# ICAN-7006-IO.net
KiCad netlist of a schematic drawn in Altium Designer
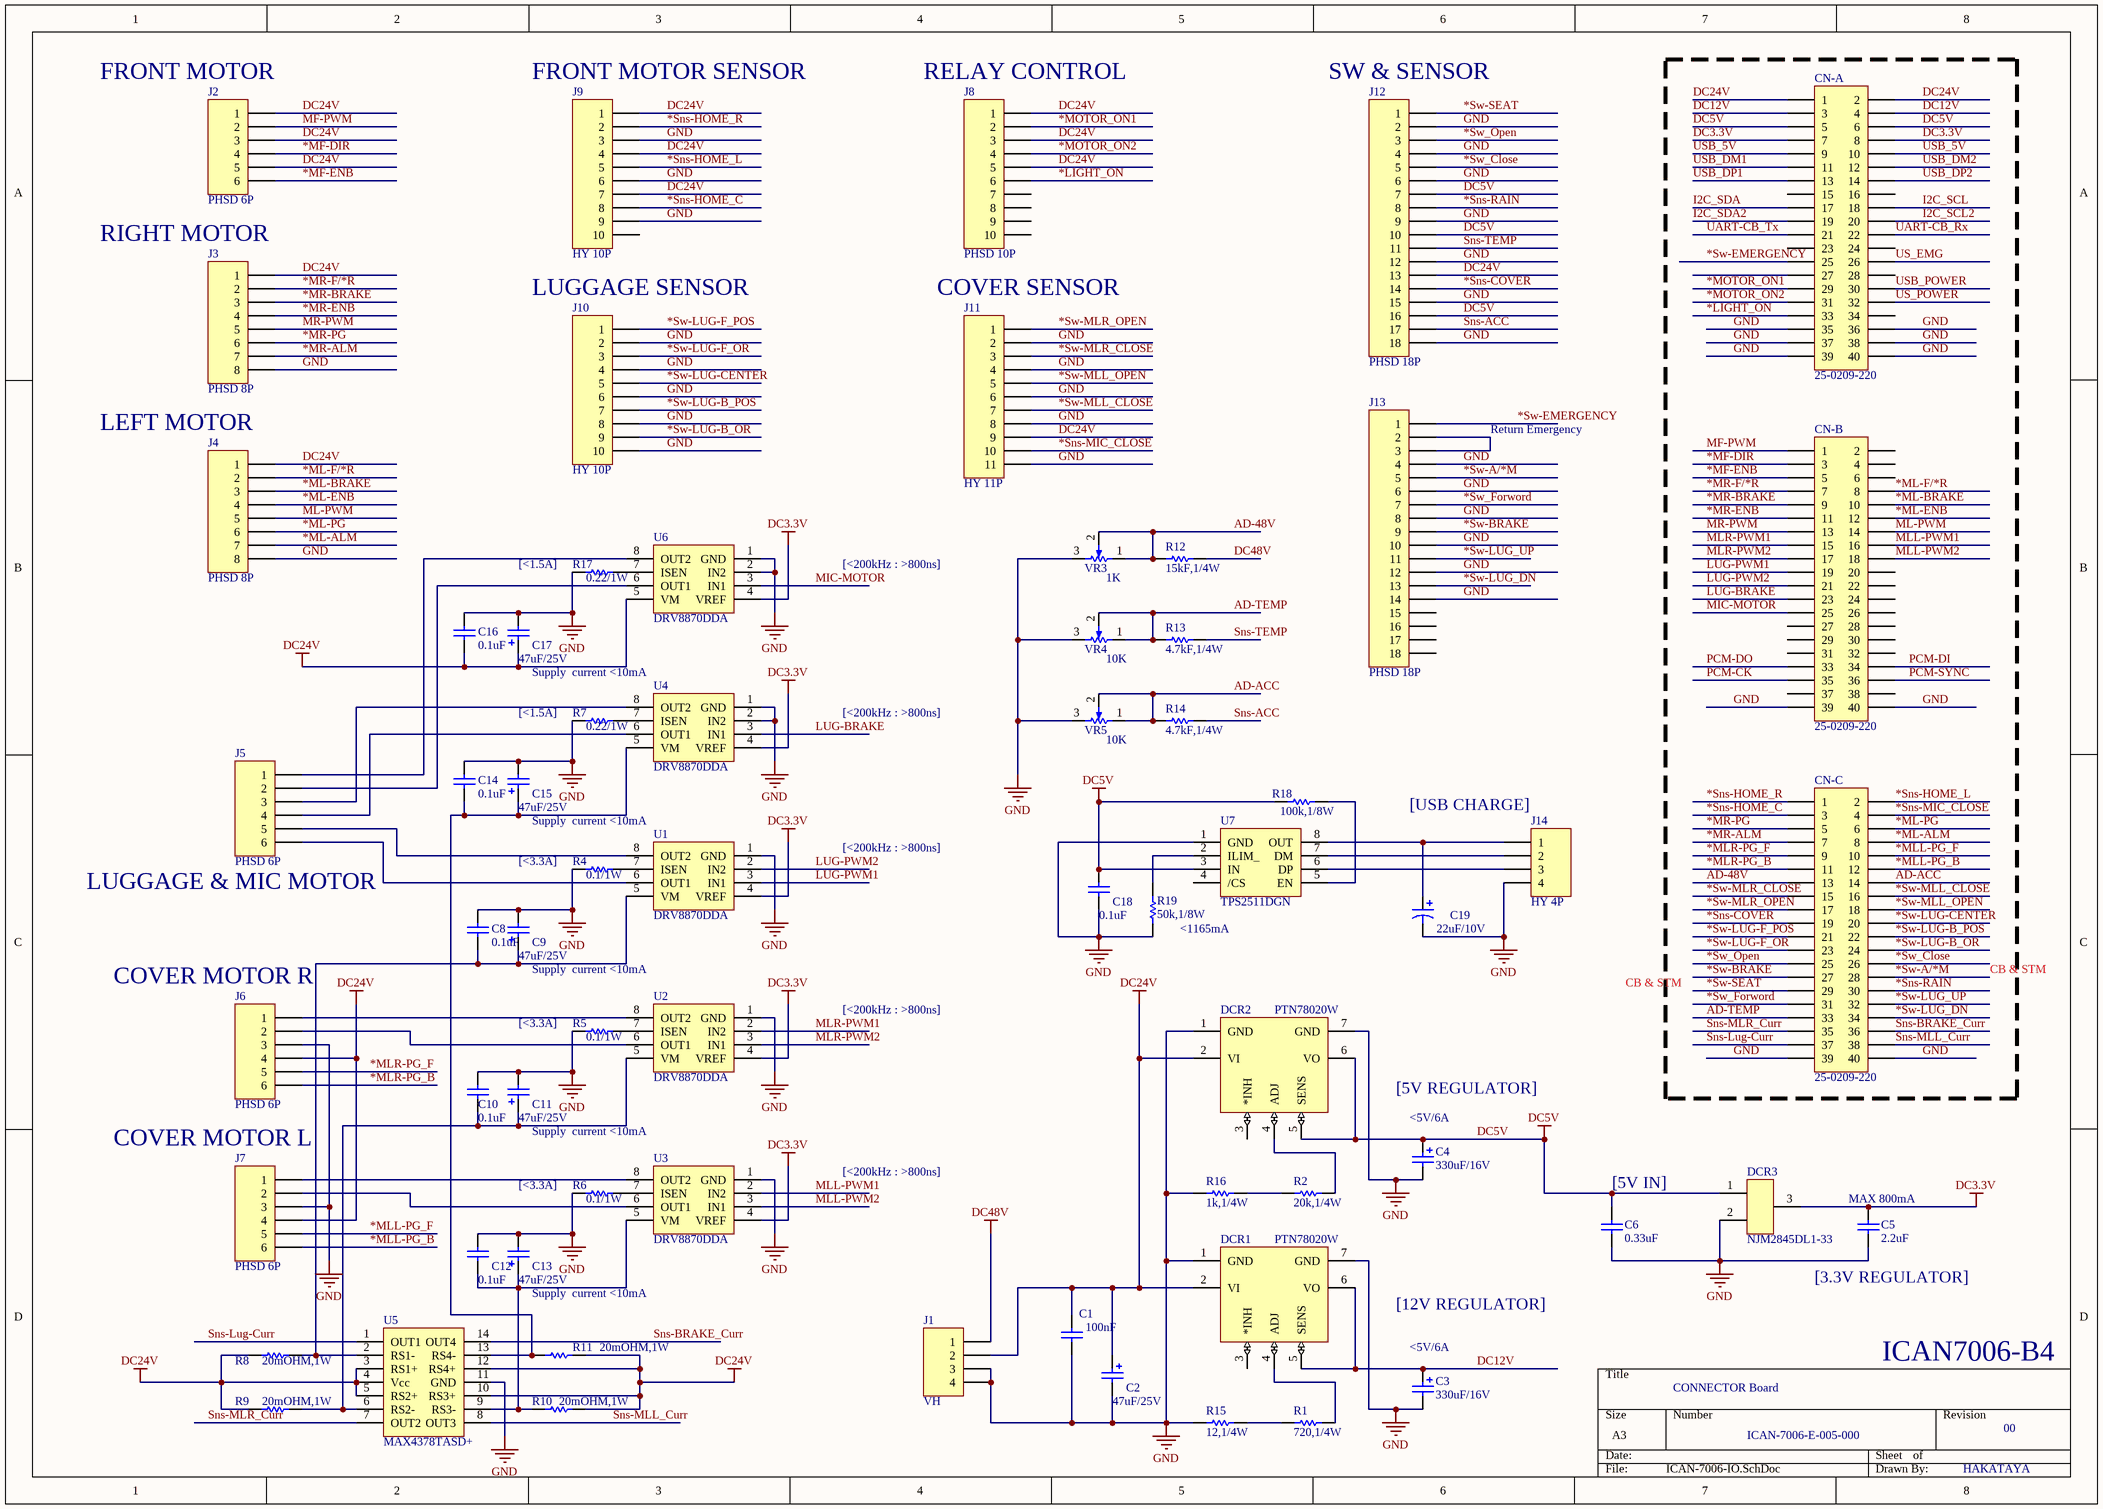
[diagram p0: ICAN-7006-IO.SchDoc]

(export (version "E")
  (design (tool "Eeschema 10.0.6"))
  (components
    (comp (ref "C1")
      (value "100nF")
      (footprint "HAKATAYA:[0805]2012")
      (description "Capacitor")
      (fields (field (name "PUBLISHER") "Altium Limited"))
      (libsource (lib "Miscellaneous Devices") (part "Cap"))
    )
    (comp (ref "C2")
      (value "47uF/25V")
      (footprint "HAKATAYA:Capa MH5 PITCH2.5mm")
      (description "Polarized Capacitor (Axial)")
      (fields (field (name "PUBLISHER") "Altium Limited"))
      (libsource (lib "Miscellaneous Devices") (part "Cap Pol2"))
    )
    (comp (ref "C3")
      (value "330uF/16V")
      (footprint "HAKATAYA:CAPA WXA PITCH 3.5mm")
      (description "Polarized Capacitor (Axial)")
      (fields (field (name "PUBLISHER") "Altium Limited"))
      (libsource (lib "Miscellaneous Devices") (part "Cap Pol2"))
    )
    (comp (ref "C4")
      (value "330uF/16V")
      (footprint "HAKATAYA:CAPA WXA PITCH 3.5mm")
      (description "Polarized Capacitor (Axial)")
      (fields (field (name "PUBLISHER") "Altium Limited"))
      (libsource (lib "Miscellaneous Devices") (part "Cap Pol2"))
    )
    (comp (ref "C5")
      (value "2.2uF")
      (footprint "[0805]2012")
      (description "Capacitor")
      (fields (field (name "PUBLISHER") "Altium Limited"))
      (libsource (lib "Miscellaneous Devices") (part "Cap Semi"))
    )
    (comp (ref "C6")
      (value "0.33uF")
      (footprint "[0805]2012")
      (description "Capacitor")
      (fields (field (name "PUBLISHER") "Altium Limited"))
      (libsource (lib "Miscellaneous Devices") (part "Cap Semi"))
    )
    (comp (ref "C8")
      (value "0.1uF")
      (footprint "HAKATAYA:[0805]2012")
      (description "Capacitor")
      (fields (field (name "PUBLISHER") "Altium Limited"))
      (libsource (lib "Miscellaneous Devices") (part "Cap"))
    )
    (comp (ref "C9")
      (value "47uF/25V")
      (footprint "HAKATAYA:Capa MH5 PITCH2.5mm")
      (description "Polarized Capacitor (Axial)")
      (fields (field (name "PUBLISHER") "Altium Limited"))
      (libsource (lib "Miscellaneous Devices") (part "Cap Pol2"))
    )
    (comp (ref "C10")
      (value "0.1uF")
      (footprint "HAKATAYA:[0805]2012")
      (description "Capacitor")
      (fields (field (name "PUBLISHER") "Altium Limited"))
      (libsource (lib "Miscellaneous Devices") (part "Cap"))
    )
    (comp (ref "C11")
      (value "47uF/25V")
      (footprint "HAKATAYA:Capa MH5 PITCH2.5mm")
      (description "Polarized Capacitor (Axial)")
      (fields (field (name "PUBLISHER") "Altium Limited"))
      (libsource (lib "Miscellaneous Devices") (part "Cap Pol2"))
    )
    (comp (ref "C12")
      (value "0.1uF")
      (footprint "HAKATAYA:[0805]2012")
      (description "Capacitor")
      (fields (field (name "PUBLISHER") "Altium Limited"))
      (libsource (lib "Miscellaneous Devices") (part "Cap"))
    )
    (comp (ref "C13")
      (value "47uF/25V")
      (footprint "HAKATAYA:Capa MH5 PITCH2.5mm")
      (description "Polarized Capacitor (Axial)")
      (fields (field (name "PUBLISHER") "Altium Limited"))
      (libsource (lib "Miscellaneous Devices") (part "Cap Pol2"))
    )
    (comp (ref "C14")
      (value "0.1uF")
      (footprint "HAKATAYA:[0805]2012")
      (description "Capacitor")
      (fields (field (name "PUBLISHER") "Altium Limited"))
      (libsource (lib "Miscellaneous Devices") (part "Cap"))
    )
    (comp (ref "C15")
      (value "47uF/25V")
      (footprint "HAKATAYA:Capa MH5 PITCH2.5mm")
      (description "Polarized Capacitor (Axial)")
      (fields (field (name "PUBLISHER") "Altium Limited"))
      (libsource (lib "Miscellaneous Devices") (part "Cap Pol2"))
    )
    (comp (ref "C16")
      (value "0.1uF")
      (footprint "HAKATAYA:[0805]2012")
      (description "Capacitor")
      (fields (field (name "PUBLISHER") "Altium Limited"))
      (libsource (lib "Miscellaneous Devices") (part "Cap"))
    )
    (comp (ref "C17")
      (value "47uF/25V")
      (footprint "HAKATAYA:Capa MH5 PITCH2.5mm")
      (description "Polarized Capacitor (Axial)")
      (fields (field (name "PUBLISHER") "Altium Limited"))
      (libsource (lib "Miscellaneous Devices") (part "Cap Pol2"))
    )
    (comp (ref "C18")
      (value "0.1uF")
      (footprint "HAKATAYA:[0805]2012")
      (description "Capacitor")
      (fields (field (name "PUBLISHER") "Altium Limited"))
      (libsource (lib "Miscellaneous Devices") (part "Cap"))
    )
    (comp (ref "C19")
      (value "22uF/10V")
      (footprint "[0805]2012")
      (description "Polarized Capacitor (Surface Mount)")
      (fields (field (name "PUBLISHER") "Altium Limited"))
      (libsource (lib "Miscellaneous Devices") (part "Cap Pol3"))
    )
    (comp (ref "CN-A")
      (value "25-0209-220")
      (footprint "HDR2X20")
      (description "Header, 20-Pin, Dual row")
      (fields (field (name "PUBLISHER") "Altium Limited"))
      (libsource (lib "Miscellaneous Connectors") (part "Header 20X2"))
    )
    (comp (ref "CN-B")
      (value "25-0209-220")
      (footprint "HDR2X20")
      (description "Header, 20-Pin, Dual row")
      (fields (field (name "PUBLISHER") "Altium Limited"))
      (libsource (lib "Miscellaneous Connectors") (part "Header 20X2"))
    )
    (comp (ref "CN-C")
      (value "25-0209-220")
      (footprint "HDR2X20")
      (description "Header, 20-Pin, Dual row")
      (fields (field (name "PUBLISHER") "Altium Limited"))
      (libsource (lib "Miscellaneous Connectors") (part "Header 20X2"))
    )
    (comp (ref "DCR1")
      (value "PTN78020W")
      (footprint "PTN78020")
      (description "REGULATOR")
      (libsource (lib "*") (part "PTN78020"))
    )
    (comp (ref "DCR2")
      (value "PTN78020W")
      (footprint "PTN78020")
      (description "REGULATOR")
      (libsource (lib "*") (part "PTN78020"))
    )
    (comp (ref "DCR3")
      (value "NJM2845DL1-33")
      (footprint "TO-252-3")
      (description "REGURATOR")
      (libsource (lib "HAKATAYA") (part "IC3"))
    )
    (comp (ref "J1")
      (value "VH")
      (footprint "HAKATAYA:VH-S4")
      (description "Header, 4-Pin")
      (fields (field (name "PUBLISHER") "Altium Limited"))
      (libsource (lib "Miscellaneous Connectors") (part "Header 4"))
    )
    (comp (ref "J2")
      (value "PHSD 6P")
      (footprint "HAKATAYA:PHSD WV03x2")
      (description "Header, 6-Pin")
      (fields (field (name "PUBLISHER") "Altium Limited"))
      (libsource (lib "Miscellaneous Connectors") (part "Header 6"))
    )
    (comp (ref "J3")
      (value "PHSD 8P")
      (footprint "HAKATAYA:PHSD WV04x2")
      (description "Header, 8-Pin")
      (fields (field (name "PUBLISHER") "Altium Limited"))
      (libsource (lib "Miscellaneous Connectors") (part "Header 8"))
    )
    (comp (ref "J4")
      (value "PHSD 8P")
      (footprint "HAKATAYA:PHSD WV04x2")
      (description "Header, 8-Pin")
      (fields (field (name "PUBLISHER") "Altium Limited"))
      (libsource (lib "Miscellaneous Connectors") (part "Header 8"))
    )
    (comp (ref "J5")
      (value "PHSD 6P")
      (footprint "HAKATAYA:PHSD WV03x2")
      (description "Header, 6-Pin")
      (fields (field (name "PUBLISHER") "Altium Limited"))
      (libsource (lib "Miscellaneous Connectors") (part "Header 6"))
    )
    (comp (ref "J6")
      (value "PHSD 6P")
      (footprint "HAKATAYA:PHSD WV03x2")
      (description "Header, 6-Pin")
      (fields (field (name "PUBLISHER") "Altium Limited"))
      (libsource (lib "Miscellaneous Connectors") (part "Header 6"))
    )
    (comp (ref "J7")
      (value "PHSD 6P")
      (footprint "HAKATAYA:PHSD WV03x2")
      (description "Header, 6-Pin")
      (fields (field (name "PUBLISHER") "Altium Limited"))
      (libsource (lib "Miscellaneous Connectors") (part "Header 6"))
    )
    (comp (ref "J8")
      (value "PHSD 10P")
      (footprint "HAKATAYA:PHSD WV05x2")
      (description "Header, 10-Pin")
      (fields (field (name "PUBLISHER") "Altium Limited"))
      (libsource (lib "Miscellaneous Connectors") (part "Header 10"))
    )
    (comp (ref "J9")
      (value "HY 10P")
      (footprint "HAKATAYA:HY-10A")
      (description "Header, 10-Pin")
      (fields (field (name "PUBLISHER") "Altium Limited"))
      (libsource (lib "Miscellaneous Connectors") (part "Header 10"))
    )
    (comp (ref "J10")
      (value "HY 10P")
      (footprint "HAKATAYA:HY-10A")
      (description "Header, 10-Pin")
      (fields (field (name "PUBLISHER") "Altium Limited"))
      (libsource (lib "Miscellaneous Connectors") (part "Header 10"))
    )
    (comp (ref "J11")
      (value "HY 11P")
      (footprint "HAKATAYA:HY-11A")
      (description "Header, 11-Pin")
      (fields (field (name "PUBLISHER") "Altium Limited"))
      (libsource (lib "Miscellaneous Connectors") (part "Header 11"))
    )
    (comp (ref "J12")
      (value "PHSD 18P")
      (footprint "HAKATAYA:PHSD WV09X2")
      (description "Header, 18-Pin")
      (fields (field (name "PUBLISHER") "Altium Limited"))
      (libsource (lib "Miscellaneous Connectors") (part "Header 18"))
    )
    (comp (ref "J13")
      (value "PHSD 18P")
      (footprint "HAKATAYA:PHSD WV09X2")
      (description "Header, 18-Pin")
      (fields (field (name "PUBLISHER") "Altium Limited"))
      (libsource (lib "Miscellaneous Connectors") (part "Header 18"))
    )
    (comp (ref "J14")
      (value "HY 4P")
      (footprint "HAKATAYA:HY-4A")
      (description "Header, 4-Pin")
      (fields (field (name "PUBLISHER") "Altium Limited"))
      (libsource (lib "") (part "Header 4_1"))
    )
    (comp (ref "R1")
      (value "720,1/4W")
      (footprint "HAKATAYA:[1206]3216")
      (description "Resistor")
      (fields (field (name "PUBLISHER") "Altium Limited"))
      (libsource (lib "Miscellaneous Devices") (part "Res1"))
    )
    (comp (ref "R2")
      (value "20k,1/4W")
      (footprint "HAKATAYA:[1206]3216")
      (description "Resistor")
      (fields (field (name "PUBLISHER") "Altium Limited"))
      (libsource (lib "Miscellaneous Devices") (part "Res1"))
    )
    (comp (ref "R4")
      (value "0.1/1W")
      (footprint "[1206]3216")
      (description "Resistor")
      (fields (field (name "PUBLISHER") "Altium Limited"))
      (libsource (lib "Miscellaneous Devices") (part "Res1"))
    )
    (comp (ref "R5")
      (value "0.1/1W")
      (footprint "[1206]3216")
      (description "Resistor")
      (fields (field (name "PUBLISHER") "Altium Limited"))
      (libsource (lib "Miscellaneous Devices") (part "Res1"))
    )
    (comp (ref "R6")
      (value "0.1/1W")
      (footprint "[1206]3216")
      (description "Resistor")
      (fields (field (name "PUBLISHER") "Altium Limited"))
      (libsource (lib "Miscellaneous Devices") (part "Res1"))
    )
    (comp (ref "R7")
      (value "0.22/1W")
      (footprint "HAKATAYA:[1206]3216")
      (description "Resistor")
      (fields (field (name "PUBLISHER") "Altium Limited"))
      (libsource (lib "Miscellaneous Devices") (part "Res1"))
    )
    (comp (ref "R8")
      (value "20mOHM,1W")
      (footprint "Miscellaneous Devices:6332[2512]")
      (description "Resistor")
      (fields (field (name "PUBLISHER") "Altium Limited"))
      (libsource (lib "Miscellaneous Devices") (part "Res1"))
    )
    (comp (ref "R9")
      (value "20mOHM,1W")
      (footprint "Miscellaneous Devices:6332[2512]")
      (description "Resistor")
      (fields (field (name "PUBLISHER") "Altium Limited"))
      (libsource (lib "Miscellaneous Devices") (part "Res1"))
    )
    (comp (ref "R10")
      (value "20mOHM,1W")
      (footprint "Miscellaneous Devices:6332[2512]")
      (description "Resistor")
      (fields (field (name "PUBLISHER") "Altium Limited"))
      (libsource (lib "Miscellaneous Devices") (part "Res1"))
    )
    (comp (ref "R11")
      (value "20mOHM,1W")
      (footprint "Miscellaneous Devices:6332[2512]")
      (description "Resistor")
      (fields (field (name "PUBLISHER") "Altium Limited"))
      (libsource (lib "Miscellaneous Devices") (part "Res1"))
    )
    (comp (ref "R12")
      (value "15kF,1/4W")
      (footprint "HAKATAYA:[1206]3216")
      (description "Resistor")
      (fields (field (name "PUBLISHER") "Altium Limited"))
      (libsource (lib "Miscellaneous Devices") (part "Res1"))
    )
    (comp (ref "R13")
      (value "4.7kF,1/4W")
      (footprint "[1206]3216")
      (description "Resistor")
      (fields (field (name "PUBLISHER") "Altium Limited"))
      (libsource (lib "Miscellaneous Devices") (part "Res1"))
    )
    (comp (ref "R14")
      (value "4.7kF,1/4W")
      (footprint "[1206]3216")
      (description "Resistor")
      (fields (field (name "PUBLISHER") "Altium Limited"))
      (libsource (lib "Miscellaneous Devices") (part "Res1"))
    )
    (comp (ref "R15")
      (value "12,1/4W")
      (footprint "HAKATAYA:[1206]3216")
      (description "Resistor")
      (fields (field (name "PUBLISHER") "Altium Limited"))
      (libsource (lib "Miscellaneous Devices") (part "Res1"))
    )
    (comp (ref "R16")
      (value "1k,1/4W")
      (footprint "HAKATAYA:[1206]3216")
      (description "Resistor")
      (fields (field (name "PUBLISHER") "Altium Limited"))
      (libsource (lib "Miscellaneous Devices") (part "Res1"))
    )
    (comp (ref "R17")
      (value "0.22/1W")
      (footprint "HAKATAYA:[1206]3216")
      (description "Resistor")
      (fields (field (name "PUBLISHER") "Altium Limited"))
      (libsource (lib "Miscellaneous Devices") (part "Res1"))
    )
    (comp (ref "R18")
      (value "100k,1/8W")
      (footprint "HAKATAYA:[0805]2012")
      (description "Resistor")
      (fields (field (name "PUBLISHER") "Altium Limited"))
      (libsource (lib "Miscellaneous Devices") (part "Res1"))
    )
    (comp (ref "R19")
      (value "50k,1/8W")
      (footprint "HAKATAYA:[0805]2012")
      (description "Resistor")
      (fields (field (name "PUBLISHER") "Altium Limited"))
      (libsource (lib "Miscellaneous Devices") (part "Res1"))
    )
    (comp (ref "U1")
      (value "DRV8870DDA")
      (footprint "TI Interface MOSFET Driver:D008_L")
      (description "Motor Driver")
      (libsource (lib "HAKATAYA") (part "IC8-WIDE"))
    )
    (comp (ref "U2")
      (value "DRV8870DDA")
      (footprint "TI Interface MOSFET Driver:D008_L")
      (description "Motor Driver")
      (libsource (lib "HAKATAYA") (part "IC8-WIDE"))
    )
    (comp (ref "U3")
      (value "DRV8870DDA")
      (footprint "TI Interface MOSFET Driver:D008_L")
      (description "Motor Driver")
      (libsource (lib "HAKATAYA") (part "IC8-WIDE"))
    )
    (comp (ref "U4")
      (value "DRV8870DDA")
      (footprint "TI Interface MOSFET Driver:D008_L")
      (description "Motor Driver")
      (libsource (lib "HAKATAYA") (part "IC8-WIDE"))
    )
    (comp (ref "U5")
      (value "MAX4378TASD+")
      (footprint "Microchip Footprints:SOIC150-14_L")
      (description "Current-Sense")
      (libsource (lib "*") (part "IC14"))
    )
    (comp (ref "U6")
      (value "DRV8870DDA")
      (footprint "TI Interface MOSFET Driver:D008_L")
      (description "Motor Driver")
      (libsource (lib "HAKATAYA") (part "IC8-WIDE"))
    )
    (comp (ref "U7")
      (value "TPS2511DGN")
      (footprint "HAKATAYA:DGN 8P")
      (description "Power Switch")
      (libsource (lib "") (part "IC8-WIDE_1"))
    )
    (comp (ref "VR3")
      (value "1K")
      (footprint "VR")
      (description "Square Trimming Potentiometer")
      (fields (field (name "PUBLISHER") "Altium Limited"))
      (libsource (lib "Miscellaneous Devices") (part "RPot SM"))
    )
    (comp (ref "VR4")
      (value "10K")
      (footprint "VR")
      (description "Square Trimming Potentiometer")
      (fields (field (name "PUBLISHER") "Altium Limited"))
      (libsource (lib "Miscellaneous Devices") (part "RPot SM"))
    )
    (comp (ref "VR5")
      (value "10K")
      (footprint "VR")
      (description "Square Trimming Potentiometer")
      (fields (field (name "PUBLISHER") "Altium Limited"))
      (libsource (lib "Miscellaneous Devices") (part "RPot SM"))
    )
  )
  (nets
    (net (code "1") (name "/*LIGHT_ON") (class "Default")
      (node (ref "CN-A") (pin "33") (pinfunction "33_33") (pintype "passive"))
      (node (ref "J8") (pin "6") (pinfunction "6_6") (pintype "passive"))
    )
    (net (code "2") (name "/*MF-DIR") (class "Default")
      (node (ref "CN-B") (pin "3") (pinfunction "3_3") (pintype "passive"))
      (node (ref "J2") (pin "4") (pinfunction "4_4") (pintype "passive"))
    )
    (net (code "3") (name "/*MF-ENB") (class "Default")
      (node (ref "CN-B") (pin "5") (pinfunction "5_5") (pintype "passive"))
      (node (ref "J2") (pin "6") (pinfunction "6_6") (pintype "passive"))
    )
    (net (code "4") (name "/*ML-ALM") (class "Default")
      (node (ref "CN-C") (pin "8") (pinfunction "8_8") (pintype "passive"))
      (node (ref "J4") (pin "7") (pinfunction "7_7") (pintype "passive"))
    )
    (net (code "5") (name "/*ML-BRAKE") (class "Default")
      (node (ref "CN-B") (pin "10") (pinfunction "10_10") (pintype "passive"))
      (node (ref "J4") (pin "3") (pinfunction "3_3") (pintype "passive"))
    )
    (net (code "6") (name "/*ML-ENB") (class "Default")
      (node (ref "CN-B") (pin "12") (pinfunction "12_12") (pintype "passive"))
      (node (ref "J4") (pin "4") (pinfunction "4_4") (pintype "passive"))
    )
    (net (code "7") (name "/*ML-F{slash}*R") (class "Default")
      (node (ref "CN-B") (pin "8") (pinfunction "8_8") (pintype "passive"))
      (node (ref "J4") (pin "2") (pinfunction "2_2") (pintype "passive"))
    )
    (net (code "8") (name "/*ML-PG") (class "Default")
      (node (ref "CN-C") (pin "6") (pinfunction "6_6") (pintype "passive"))
      (node (ref "J4") (pin "6") (pinfunction "6_6") (pintype "passive"))
    )
    (net (code "9") (name "/*MLL-PG_B") (class "Default")
      (node (ref "CN-C") (pin "12") (pinfunction "12_12") (pintype "passive"))
      (node (ref "J7") (pin "6") (pinfunction "6_6") (pintype "passive"))
    )
    (net (code "10") (name "/*MLL-PG_F") (class "Default")
      (node (ref "CN-C") (pin "10") (pinfunction "10_10") (pintype "passive"))
      (node (ref "J7") (pin "5") (pinfunction "5_5") (pintype "passive"))
    )
    (net (code "11") (name "/*MLR-PG_B") (class "Default")
      (node (ref "CN-C") (pin "11") (pinfunction "11_11") (pintype "passive"))
      (node (ref "J6") (pin "6") (pinfunction "6_6") (pintype "passive"))
    )
    (net (code "12") (name "/*MLR-PG_F") (class "Default")
      (node (ref "CN-C") (pin "9") (pinfunction "9_9") (pintype "passive"))
      (node (ref "J6") (pin "5") (pinfunction "5_5") (pintype "passive"))
    )
    (net (code "13") (name "/*MOTOR_ON1") (class "Default")
      (node (ref "CN-A") (pin "29") (pinfunction "29_29") (pintype "passive"))
      (node (ref "J8") (pin "2") (pinfunction "2_2") (pintype "passive"))
    )
    (net (code "14") (name "/*MOTOR_ON2") (class "Default")
      (node (ref "CN-A") (pin "31") (pinfunction "31_31") (pintype "passive"))
      (node (ref "J8") (pin "4") (pinfunction "4_4") (pintype "passive"))
    )
    (net (code "15") (name "/*MR-ALM") (class "Default")
      (node (ref "CN-C") (pin "7") (pinfunction "7_7") (pintype "passive"))
      (node (ref "J3") (pin "7") (pinfunction "7_7") (pintype "passive"))
    )
    (net (code "16") (name "/*MR-BRAKE") (class "Default")
      (node (ref "CN-B") (pin "9") (pinfunction "9_9") (pintype "passive"))
      (node (ref "J3") (pin "3") (pinfunction "3_3") (pintype "passive"))
    )
    (net (code "17") (name "/*MR-ENB") (class "Default")
      (node (ref "CN-B") (pin "11") (pinfunction "11_11") (pintype "passive"))
      (node (ref "J3") (pin "4") (pinfunction "4_4") (pintype "passive"))
    )
    (net (code "18") (name "/*MR-F{slash}*R") (class "Default")
      (node (ref "CN-B") (pin "7") (pinfunction "7_7") (pintype "passive"))
      (node (ref "J3") (pin "2") (pinfunction "2_2") (pintype "passive"))
    )
    (net (code "19") (name "/*MR-PG") (class "Default")
      (node (ref "CN-C") (pin "5") (pinfunction "5_5") (pintype "passive"))
      (node (ref "J3") (pin "6") (pinfunction "6_6") (pintype "passive"))
    )
    (net (code "20") (name "/*Sns-COVER") (class "Default")
      (node (ref "CN-C") (pin "19") (pinfunction "19_19") (pintype "passive"))
      (node (ref "J12") (pin "14") (pinfunction "14_14") (pintype "passive"))
    )
    (net (code "21") (name "/*Sns-HOME_C") (class "Default")
      (node (ref "CN-C") (pin "3") (pinfunction "3_3") (pintype "passive"))
      (node (ref "J9") (pin "8") (pinfunction "8_8") (pintype "passive"))
    )
    (net (code "22") (name "/*Sns-HOME_L") (class "Default")
      (node (ref "CN-C") (pin "2") (pinfunction "2_2") (pintype "passive"))
      (node (ref "J9") (pin "5") (pinfunction "5_5") (pintype "passive"))
    )
    (net (code "23") (name "/*Sns-HOME_R") (class "Default")
      (node (ref "CN-C") (pin "1") (pinfunction "1_1") (pintype "passive"))
      (node (ref "J9") (pin "2") (pinfunction "2_2") (pintype "passive"))
    )
    (net (code "24") (name "/*Sns-MIC_CLOSE") (class "Default")
      (node (ref "CN-C") (pin "4") (pinfunction "4_4") (pintype "passive"))
      (node (ref "J11") (pin "10") (pinfunction "10_10") (pintype "passive"))
    )
    (net (code "25") (name "/*Sns-RAIN") (class "Default")
      (node (ref "CN-C") (pin "30") (pinfunction "30_30") (pintype "passive"))
      (node (ref "J12") (pin "8") (pinfunction "8_8") (pintype "passive"))
    )
    (net (code "26") (name "/*Sw-A{slash}*M") (class "Default")
      (node (ref "CN-C") (pin "28") (pinfunction "28_28") (pintype "passive"))
      (node (ref "J13") (pin "5") (pinfunction "5_5") (pintype "passive"))
    )
    (net (code "27") (name "/*Sw-BRAKE") (class "Default")
      (node (ref "CN-C") (pin "27") (pinfunction "27_27") (pintype "passive"))
      (node (ref "J13") (pin "9") (pinfunction "9_9") (pintype "passive"))
    )
    (net (code "28") (name "/*Sw-EMERGENCY") (class "Default")
      (node (ref "CN-A") (pin "25") (pinfunction "25_25") (pintype "passive"))
      (node (ref "J13") (pin "1") (pinfunction "1_1") (pintype "passive"))
    )
    (net (code "29") (name "/*Sw-LUG-B_OR") (class "Default")
      (node (ref "CN-C") (pin "24") (pinfunction "24_24") (pintype "passive"))
      (node (ref "J10") (pin "9") (pinfunction "9_9") (pintype "passive"))
    )
    (net (code "30") (name "/*Sw-LUG-B_POS") (class "Default")
      (node (ref "CN-C") (pin "22") (pinfunction "22_22") (pintype "passive"))
      (node (ref "J10") (pin "7") (pinfunction "7_7") (pintype "passive"))
    )
    (net (code "31") (name "/*Sw-LUG-CENTER") (class "Default")
      (node (ref "CN-C") (pin "20") (pinfunction "20_20") (pintype "passive"))
      (node (ref "J10") (pin "5") (pinfunction "5_5") (pintype "passive"))
    )
    (net (code "32") (name "/*Sw-LUG-F_OR") (class "Default")
      (node (ref "CN-C") (pin "23") (pinfunction "23_23") (pintype "passive"))
      (node (ref "J10") (pin "3") (pinfunction "3_3") (pintype "passive"))
    )
    (net (code "33") (name "/*Sw-LUG-F_POS") (class "Default")
      (node (ref "CN-C") (pin "21") (pinfunction "21_21") (pintype "passive"))
      (node (ref "J10") (pin "1") (pinfunction "1_1") (pintype "passive"))
    )
    (net (code "34") (name "/*Sw-LUG_DN") (class "Default")
      (node (ref "CN-C") (pin "34") (pinfunction "34_34") (pintype "passive"))
      (node (ref "J13") (pin "13") (pinfunction "13_13") (pintype "passive"))
    )
    (net (code "35") (name "/*Sw-LUG_UP") (class "Default")
      (node (ref "CN-C") (pin "32") (pinfunction "32_32") (pintype "passive"))
      (node (ref "J13") (pin "11") (pinfunction "11_11") (pintype "passive"))
    )
    (net (code "36") (name "/*Sw-MLL_CLOSE") (class "Default")
      (node (ref "CN-C") (pin "16") (pinfunction "16_16") (pintype "passive"))
      (node (ref "J11") (pin "7") (pinfunction "7_7") (pintype "passive"))
    )
    (net (code "37") (name "/*Sw-MLL_OPEN") (class "Default")
      (node (ref "CN-C") (pin "18") (pinfunction "18_18") (pintype "passive"))
      (node (ref "J11") (pin "5") (pinfunction "5_5") (pintype "passive"))
    )
    (net (code "38") (name "/*Sw-MLR_CLOSE") (class "Default")
      (node (ref "CN-C") (pin "15") (pinfunction "15_15") (pintype "passive"))
      (node (ref "J11") (pin "3") (pinfunction "3_3") (pintype "passive"))
    )
    (net (code "39") (name "/*Sw-MLR_OPEN") (class "Default")
      (node (ref "CN-C") (pin "17") (pinfunction "17_17") (pintype "passive"))
      (node (ref "J11") (pin "1") (pinfunction "1_1") (pintype "passive"))
    )
    (net (code "40") (name "/*Sw-SEAT") (class "Default")
      (node (ref "CN-C") (pin "29") (pinfunction "29_29") (pintype "passive"))
      (node (ref "J12") (pin "1") (pinfunction "1_1") (pintype "passive"))
    )
    (net (code "41") (name "/*Sw_Close") (class "Default")
      (node (ref "CN-C") (pin "26") (pinfunction "26_26") (pintype "passive"))
      (node (ref "J12") (pin "5") (pinfunction "5_5") (pintype "passive"))
    )
    (net (code "42") (name "/*Sw_Forword") (class "Default")
      (node (ref "CN-C") (pin "31") (pinfunction "31_31") (pintype "passive"))
      (node (ref "J13") (pin "7") (pinfunction "7_7") (pintype "passive"))
    )
    (net (code "43") (name "/*Sw_Open") (class "Default")
      (node (ref "CN-C") (pin "25") (pinfunction "25_25") (pintype "passive"))
      (node (ref "J12") (pin "3") (pinfunction "3_3") (pintype "passive"))
    )
    (net (code "44") (name "/AD-48V") (class "Default")
      (node (ref "CN-C") (pin "13") (pinfunction "13_13") (pintype "passive"))
      (node (ref "R12") (pin "1") (pinfunction "1_1") (pintype "passive"))
      (node (ref "VR3") (pin "1") (pinfunction "1_1") (pintype "passive"))
      (node (ref "VR3") (pin "2") (pinfunction "3_2") (pintype "passive"))
    )
    (net (code "45") (name "/AD-ACC") (class "Default")
      (node (ref "CN-C") (pin "14") (pinfunction "14_14") (pintype "passive"))
      (node (ref "R14") (pin "1") (pinfunction "1_1") (pintype "passive"))
      (node (ref "VR5") (pin "1") (pinfunction "1_1") (pintype "passive"))
      (node (ref "VR5") (pin "2") (pinfunction "3_2") (pintype "passive"))
    )
    (net (code "46") (name "/AD-TEMP") (class "Default")
      (node (ref "CN-C") (pin "33") (pinfunction "33_33") (pintype "passive"))
      (node (ref "R13") (pin "1") (pinfunction "1_1") (pintype "passive"))
      (node (ref "VR4") (pin "1") (pinfunction "1_1") (pintype "passive"))
      (node (ref "VR4") (pin "2") (pinfunction "3_2") (pintype "passive"))
    )
    (net (code "47") (name "/DC12V") (class "Default")
      (node (ref "C3") (pin "1") (pinfunction "1_1") (pintype "passive"))
      (node (ref "CN-A") (pin "3") (pinfunction "3_3") (pintype "passive"))
      (node (ref "CN-A") (pin "4") (pinfunction "4_4") (pintype "passive"))
      (node (ref "DCR1") (pin "5") (pinfunction "SENS_5") (pintype "bidirectional"))
      (node (ref "DCR1") (pin "6") (pinfunction "VO_6") (pintype "power_in"))
    )
    (net (code "48") (name "/I2C_SCL") (class "Default")
      (node (ref "CN-A") (pin "18") (pinfunction "18_18") (pintype "passive"))
    )
    (net (code "49") (name "/I2C_SCL2") (class "Default")
      (node (ref "CN-A") (pin "20") (pinfunction "20_20") (pintype "passive"))
    )
    (net (code "50") (name "/I2C_SDA") (class "Default")
      (node (ref "CN-A") (pin "17") (pinfunction "17_17") (pintype "passive"))
    )
    (net (code "51") (name "/I2C_SDA2") (class "Default")
      (node (ref "CN-A") (pin "19") (pinfunction "19_19") (pintype "passive"))
    )
    (net (code "52") (name "/LUG-BRAKE") (class "Default")
      (node (ref "CN-B") (pin "23") (pinfunction "23_23") (pintype "passive"))
      (node (ref "U4") (pin "3") (pinfunction "IN1_3") (pintype "passive"))
    )
    (net (code "53") (name "/LUG-PWM1") (class "Default")
      (node (ref "CN-B") (pin "19") (pinfunction "19_19") (pintype "passive"))
      (node (ref "U1") (pin "3") (pinfunction "IN1_3") (pintype "passive"))
    )
    (net (code "54") (name "/LUG-PWM2") (class "Default")
      (node (ref "CN-B") (pin "21") (pinfunction "21_21") (pintype "passive"))
      (node (ref "U1") (pin "2") (pinfunction "IN2_2") (pintype "passive"))
    )
    (net (code "55") (name "/MF-PWM") (class "Default")
      (node (ref "CN-B") (pin "1") (pinfunction "1_1") (pintype "passive"))
      (node (ref "J2") (pin "2") (pinfunction "2_2") (pintype "passive"))
    )
    (net (code "56") (name "/MIC-MOTOR") (class "Default")
      (node (ref "CN-B") (pin "25") (pinfunction "25_25") (pintype "passive"))
      (node (ref "U6") (pin "3") (pinfunction "IN1_3") (pintype "passive"))
    )
    (net (code "57") (name "/ML-PWM") (class "Default")
      (node (ref "CN-B") (pin "14") (pinfunction "14_14") (pintype "passive"))
      (node (ref "J4") (pin "5") (pinfunction "5_5") (pintype "passive"))
    )
    (net (code "58") (name "/MLL-PWM1") (class "Default")
      (node (ref "CN-B") (pin "16") (pinfunction "16_16") (pintype "passive"))
      (node (ref "U3") (pin "2") (pinfunction "IN2_2") (pintype "passive"))
    )
    (net (code "59") (name "/MLL-PWM2") (class "Default")
      (node (ref "CN-B") (pin "18") (pinfunction "18_18") (pintype "passive"))
      (node (ref "U3") (pin "3") (pinfunction "IN1_3") (pintype "passive"))
    )
    (net (code "60") (name "/MLR-PWM1") (class "Default")
      (node (ref "CN-B") (pin "15") (pinfunction "15_15") (pintype "passive"))
      (node (ref "U2") (pin "2") (pinfunction "IN2_2") (pintype "passive"))
    )
    (net (code "61") (name "/MLR-PWM2") (class "Default")
      (node (ref "CN-B") (pin "17") (pinfunction "17_17") (pintype "passive"))
      (node (ref "U2") (pin "3") (pinfunction "IN1_3") (pintype "passive"))
    )
    (net (code "62") (name "/MR-PWM") (class "Default")
      (node (ref "CN-B") (pin "13") (pinfunction "13_13") (pintype "passive"))
      (node (ref "J3") (pin "5") (pinfunction "5_5") (pintype "passive"))
    )
    (net (code "63") (name "/PCM-CK") (class "Default")
      (node (ref "CN-B") (pin "35") (pinfunction "35_35") (pintype "passive"))
    )
    (net (code "64") (name "/PCM-DI") (class "Default")
      (node (ref "CN-B") (pin "34") (pinfunction "34_34") (pintype "passive"))
    )
    (net (code "65") (name "/PCM-DO") (class "Default")
      (node (ref "CN-B") (pin "33") (pinfunction "33_33") (pintype "passive"))
    )
    (net (code "66") (name "/PCM-SYNC") (class "Default")
      (node (ref "CN-B") (pin "36") (pinfunction "36_36") (pintype "passive"))
    )
    (net (code "67") (name "/Sns-ACC") (class "Default")
      (node (ref "J12") (pin "17") (pinfunction "17_17") (pintype "passive"))
      (node (ref "R14") (pin "2") (pinfunction "2_2") (pintype "passive"))
    )
    (net (code "68") (name "/Sns-BRAKE_Curr") (class "Default")
      (node (ref "CN-C") (pin "36") (pinfunction "36_36") (pintype "passive"))
      (node (ref "U5") (pin "14") (pinfunction "OUT4_14") (pintype "passive"))
    )
    (net (code "69") (name "/Sns-Lug-Curr") (class "Default")
      (node (ref "CN-C") (pin "37") (pinfunction "37_37") (pintype "passive"))
      (node (ref "U5") (pin "1") (pinfunction "OUT1_1") (pintype "passive"))
    )
    (net (code "70") (name "/Sns-MLL_Curr") (class "Default")
      (node (ref "CN-C") (pin "38") (pinfunction "38_38") (pintype "passive"))
      (node (ref "U5") (pin "8") (pinfunction "OUT3_8") (pintype "passive"))
    )
    (net (code "71") (name "/Sns-MLR_Curr") (class "Default")
      (node (ref "CN-C") (pin "35") (pinfunction "35_35") (pintype "passive"))
      (node (ref "U5") (pin "7") (pinfunction "OUT2_7") (pintype "passive"))
    )
    (net (code "72") (name "/Sns-TEMP") (class "Default")
      (node (ref "J12") (pin "11") (pinfunction "11_11") (pintype "passive"))
      (node (ref "R13") (pin "2") (pinfunction "2_2") (pintype "passive"))
    )
    (net (code "73") (name "/UART-CB_Rx") (class "Default")
      (node (ref "CN-A") (pin "22") (pinfunction "22_22") (pintype "passive"))
    )
    (net (code "74") (name "/UART-CB_Tx") (class "Default")
      (node (ref "CN-A") (pin "21") (pinfunction "21_21") (pintype "passive"))
    )
    (net (code "75") (name "/USB_5V") (class "Default")
      (node (ref "CN-A") (pin "10") (pinfunction "10_10") (pintype "passive"))
      (node (ref "CN-A") (pin "9") (pinfunction "9_9") (pintype "passive"))
    )
    (net (code "76") (name "/USB_DM1") (class "Default")
      (node (ref "CN-A") (pin "11") (pinfunction "11_11") (pintype "passive"))
    )
    (net (code "77") (name "/USB_DM2") (class "Default")
      (node (ref "CN-A") (pin "12") (pinfunction "12_12") (pintype "passive"))
    )
    (net (code "78") (name "/USB_DP1") (class "Default")
      (node (ref "CN-A") (pin "13") (pinfunction "13_13") (pintype "passive"))
    )
    (net (code "79") (name "/USB_DP2") (class "Default")
      (node (ref "CN-A") (pin "14") (pinfunction "14_14") (pintype "passive"))
    )
    (net (code "80") (name "/USB_POWER") (class "Default")
      (node (ref "CN-A") (pin "30") (pinfunction "30_30") (pintype "passive"))
    )
    (net (code "81") (name "/US_EMG") (class "Default")
      (node (ref "CN-A") (pin "26") (pinfunction "26_26") (pintype "passive"))
    )
    (net (code "82") (name "/US_POWER") (class "Default")
      (node (ref "CN-A") (pin "32") (pinfunction "32_32") (pintype "passive"))
    )
    (net (code "83") (name "DC3.3V") (class "Default")
      (node (ref "C5") (pin "2") (pinfunction "2_2") (pintype "passive"))
      (node (ref "CN-A") (pin "7") (pinfunction "7_7") (pintype "passive"))
      (node (ref "CN-A") (pin "8") (pinfunction "8_8") (pintype "passive"))
      (node (ref "DCR3") (pin "3") (pinfunction "3_3") (pintype "power_in"))
      (node (ref "U1") (pin "4") (pinfunction "VREF_4") (pintype "passive"))
      (node (ref "U2") (pin "4") (pinfunction "VREF_4") (pintype "passive"))
      (node (ref "U3") (pin "4") (pinfunction "VREF_4") (pintype "passive"))
      (node (ref "U4") (pin "4") (pinfunction "VREF_4") (pintype "passive"))
      (node (ref "U6") (pin "4") (pinfunction "VREF_4") (pintype "passive"))
    )
    (net (code "84") (name "DC5V") (class "Default")
      (node (ref "C18") (pin "2") (pinfunction "2_2") (pintype "passive"))
      (node (ref "C4") (pin "1") (pinfunction "1_1") (pintype "passive"))
      (node (ref "C6") (pin "2") (pinfunction "2_2") (pintype "passive"))
      (node (ref "CN-A") (pin "5") (pinfunction "5_5") (pintype "passive"))
      (node (ref "CN-A") (pin "6") (pinfunction "6_6") (pintype "passive"))
      (node (ref "DCR2") (pin "5") (pinfunction "SENS_5") (pintype "bidirectional"))
      (node (ref "DCR2") (pin "6") (pinfunction "VO_6") (pintype "power_in"))
      (node (ref "DCR3") (pin "1") (pinfunction "1_1") (pintype "power_in"))
      (node (ref "J12") (pin "10") (pinfunction "10_10") (pintype "passive"))
      (node (ref "J12") (pin "16") (pinfunction "16_16") (pintype "passive"))
      (node (ref "J12") (pin "7") (pinfunction "7_7") (pintype "passive"))
      (node (ref "R18") (pin "1") (pinfunction "1_1") (pintype "passive"))
      (node (ref "U7") (pin "3") (pinfunction "IN_3") (pintype "passive"))
    )
    (net (code "85") (name "DC24V") (class "Default")
      (node (ref "C1") (pin "2") (pinfunction "2_2") (pintype "passive"))
      (node (ref "C16") (pin "1") (pinfunction "1_1") (pintype "passive"))
      (node (ref "C17") (pin "1") (pinfunction "1_1") (pintype "passive"))
      (node (ref "C2") (pin "1") (pinfunction "1_1") (pintype "passive"))
      (node (ref "CN-A") (pin "1") (pinfunction "1_1") (pintype "passive"))
      (node (ref "CN-A") (pin "2") (pinfunction "2_2") (pintype "passive"))
      (node (ref "DCR1") (pin "2") (pinfunction "VI_2") (pintype "power_in"))
      (node (ref "DCR2") (pin "2") (pinfunction "VI_2") (pintype "power_in"))
      (node (ref "J1") (pin "2") (pinfunction "2_2") (pintype "passive"))
      (node (ref "J11") (pin "9") (pinfunction "9_9") (pintype "passive"))
      (node (ref "J12") (pin "13") (pinfunction "13_13") (pintype "passive"))
      (node (ref "J2") (pin "1") (pinfunction "1_1") (pintype "passive"))
      (node (ref "J2") (pin "3") (pinfunction "3_3") (pintype "passive"))
      (node (ref "J2") (pin "5") (pinfunction "5_5") (pintype "passive"))
      (node (ref "J3") (pin "1") (pinfunction "1_1") (pintype "passive"))
      (node (ref "J4") (pin "1") (pinfunction "1_1") (pintype "passive"))
      (node (ref "J6") (pin "4") (pinfunction "4_4") (pintype "passive"))
      (node (ref "J7") (pin "4") (pinfunction "4_4") (pintype "passive"))
      (node (ref "J8") (pin "1") (pinfunction "1_1") (pintype "passive"))
      (node (ref "J8") (pin "3") (pinfunction "3_3") (pintype "passive"))
      (node (ref "J8") (pin "5") (pinfunction "5_5") (pintype "passive"))
      (node (ref "J9") (pin "1") (pinfunction "1_1") (pintype "passive"))
      (node (ref "J9") (pin "4") (pinfunction "4_4") (pintype "passive"))
      (node (ref "J9") (pin "7") (pinfunction "7_7") (pintype "passive"))
      (node (ref "R10") (pin "2") (pinfunction "2_2") (pintype "passive"))
      (node (ref "R11") (pin "2") (pinfunction "2_2") (pintype "passive"))
      (node (ref "R8") (pin "1") (pinfunction "1_1") (pintype "passive"))
      (node (ref "R9") (pin "1") (pinfunction "1_1") (pintype "passive"))
      (node (ref "U5") (pin "10") (pinfunction "RS3+_10") (pintype "passive"))
      (node (ref "U5") (pin "12") (pinfunction "RS4+_12") (pintype "passive"))
      (node (ref "U5") (pin "3") (pinfunction "RS1+_3") (pintype "passive"))
      (node (ref "U5") (pin "4") (pinfunction "Vcc_4") (pintype "passive"))
      (node (ref "U5") (pin "5") (pinfunction "RS2+_5") (pintype "passive"))
      (node (ref "U6") (pin "5") (pinfunction "VM_5") (pintype "passive"))
    )
    (net (code "86") (name "DC48V") (class "Default")
      (node (ref "J1") (pin "1") (pinfunction "1_1") (pintype "passive"))
      (node (ref "R12") (pin "2") (pinfunction "2_2") (pintype "passive"))
    )
    (net (code "87") (name "GND") (class "Default")
      (node (ref "C1") (pin "1") (pinfunction "1_1") (pintype "passive"))
      (node (ref "C10") (pin "2") (pinfunction "2_2") (pintype "passive"))
      (node (ref "C11") (pin "2") (pinfunction "2_2") (pintype "passive"))
      (node (ref "C12") (pin "2") (pinfunction "2_2") (pintype "passive"))
      (node (ref "C13") (pin "2") (pinfunction "2_2") (pintype "passive"))
      (node (ref "C14") (pin "2") (pinfunction "2_2") (pintype "passive"))
      (node (ref "C15") (pin "2") (pinfunction "2_2") (pintype "passive"))
      (node (ref "C16") (pin "2") (pinfunction "2_2") (pintype "passive"))
      (node (ref "C17") (pin "2") (pinfunction "2_2") (pintype "passive"))
      (node (ref "C18") (pin "1") (pinfunction "1_1") (pintype "passive"))
      (node (ref "C19") (pin "2") (pinfunction "2_2") (pintype "passive"))
      (node (ref "C2") (pin "2") (pinfunction "2_2") (pintype "passive"))
      (node (ref "C3") (pin "2") (pinfunction "2_2") (pintype "passive"))
      (node (ref "C4") (pin "2") (pinfunction "2_2") (pintype "passive"))
      (node (ref "C5") (pin "1") (pinfunction "1_1") (pintype "passive"))
      (node (ref "C6") (pin "1") (pinfunction "1_1") (pintype "passive"))
      (node (ref "C8") (pin "2") (pinfunction "2_2") (pintype "passive"))
      (node (ref "C9") (pin "2") (pinfunction "2_2") (pintype "passive"))
      (node (ref "CN-A") (pin "35") (pinfunction "35_35") (pintype "passive"))
      (node (ref "CN-A") (pin "36") (pinfunction "36_36") (pintype "passive"))
      (node (ref "CN-A") (pin "37") (pinfunction "37_37") (pintype "passive"))
      (node (ref "CN-A") (pin "38") (pinfunction "38_38") (pintype "passive"))
      (node (ref "CN-A") (pin "39") (pinfunction "39_39") (pintype "passive"))
      (node (ref "CN-A") (pin "40") (pinfunction "40_40") (pintype "passive"))
      (node (ref "CN-B") (pin "39") (pinfunction "39_39") (pintype "passive"))
      (node (ref "CN-B") (pin "40") (pinfunction "40_40") (pintype "passive"))
      (node (ref "CN-C") (pin "39") (pinfunction "39_39") (pintype "passive"))
      (node (ref "CN-C") (pin "40") (pinfunction "40_40") (pintype "passive"))
      (node (ref "DCR1") (pin "1") (pinfunction "GND_1") (pintype "power_in"))
      (node (ref "DCR1") (pin "7") (pinfunction "GND_7") (pintype "power_in"))
      (node (ref "DCR2") (pin "1") (pinfunction "GND_1") (pintype "power_in"))
      (node (ref "DCR2") (pin "7") (pinfunction "GND_7") (pintype "power_in"))
      (node (ref "DCR3") (pin "2") (pinfunction "2_2") (pintype "power_in"))
      (node (ref "J1") (pin "3") (pinfunction "3_3") (pintype "passive"))
      (node (ref "J1") (pin "4") (pinfunction "4_4") (pintype "passive"))
      (node (ref "J10") (pin "10") (pinfunction "10_10") (pintype "passive"))
      (node (ref "J10") (pin "2") (pinfunction "2_2") (pintype "passive"))
      (node (ref "J10") (pin "4") (pinfunction "4_4") (pintype "passive"))
      (node (ref "J10") (pin "6") (pinfunction "6_6") (pintype "passive"))
      (node (ref "J10") (pin "8") (pinfunction "8_8") (pintype "passive"))
      (node (ref "J11") (pin "11") (pinfunction "11_11") (pintype "passive"))
      (node (ref "J11") (pin "2") (pinfunction "2_2") (pintype "passive"))
      (node (ref "J11") (pin "4") (pinfunction "4_4") (pintype "passive"))
      (node (ref "J11") (pin "6") (pinfunction "6_6") (pintype "passive"))
      (node (ref "J11") (pin "8") (pinfunction "8_8") (pintype "passive"))
      (node (ref "J12") (pin "12") (pinfunction "12_12") (pintype "passive"))
      (node (ref "J12") (pin "15") (pinfunction "15_15") (pintype "passive"))
      (node (ref "J12") (pin "18") (pinfunction "18_18") (pintype "passive"))
      (node (ref "J12") (pin "2") (pinfunction "2_2") (pintype "passive"))
      (node (ref "J12") (pin "4") (pinfunction "4_4") (pintype "passive"))
      (node (ref "J12") (pin "6") (pinfunction "6_6") (pintype "passive"))
      (node (ref "J12") (pin "9") (pinfunction "9_9") (pintype "passive"))
      (node (ref "J13") (pin "10") (pinfunction "10_10") (pintype "passive"))
      (node (ref "J13") (pin "12") (pinfunction "12_12") (pintype "passive"))
      (node (ref "J13") (pin "14") (pinfunction "14_14") (pintype "passive"))
      (node (ref "J13") (pin "4") (pinfunction "4_4") (pintype "passive"))
      (node (ref "J13") (pin "6") (pinfunction "6_6") (pintype "passive"))
      (node (ref "J13") (pin "8") (pinfunction "8_8") (pintype "passive"))
      (node (ref "J14") (pin "4") (pinfunction "4_4") (pintype "passive"))
      (node (ref "J3") (pin "8") (pinfunction "8_8") (pintype "passive"))
      (node (ref "J4") (pin "8") (pinfunction "8_8") (pintype "passive"))
      (node (ref "J6") (pin "3") (pinfunction "3_3") (pintype "passive"))
      (node (ref "J7") (pin "3") (pinfunction "3_3") (pintype "passive"))
      (node (ref "J9") (pin "3") (pinfunction "3_3") (pintype "passive"))
      (node (ref "J9") (pin "6") (pinfunction "6_6") (pintype "passive"))
      (node (ref "J9") (pin "9") (pinfunction "9_9") (pintype "passive"))
      (node (ref "R15") (pin "1") (pinfunction "1_1") (pintype "passive"))
      (node (ref "R16") (pin "1") (pinfunction "1_1") (pintype "passive"))
      (node (ref "R17") (pin "1") (pinfunction "1_1") (pintype "passive"))
      (node (ref "R19") (pin "1") (pinfunction "1_1") (pintype "passive"))
      (node (ref "R4") (pin "1") (pinfunction "1_1") (pintype "passive"))
      (node (ref "R5") (pin "1") (pinfunction "1_1") (pintype "passive"))
      (node (ref "R6") (pin "1") (pinfunction "1_1") (pintype "passive"))
      (node (ref "R7") (pin "1") (pinfunction "1_1") (pintype "passive"))
      (node (ref "U1") (pin "1") (pinfunction "GND_1") (pintype "passive"))
      (node (ref "U2") (pin "1") (pinfunction "GND_1") (pintype "passive"))
      (node (ref "U3") (pin "1") (pinfunction "GND_1") (pintype "passive"))
      (node (ref "U4") (pin "1") (pinfunction "GND_1") (pintype "passive"))
      (node (ref "U4") (pin "2") (pinfunction "IN2_2") (pintype "passive"))
      (node (ref "U5") (pin "11") (pinfunction "GND_11") (pintype "passive"))
      (node (ref "U6") (pin "1") (pinfunction "GND_1") (pintype "passive"))
      (node (ref "U6") (pin "2") (pinfunction "IN2_2") (pintype "passive"))
      (node (ref "U7") (pin "1") (pinfunction "GND_1") (pintype "passive"))
      (node (ref "VR3") (pin "3") (pinfunction "2_3") (pintype "passive"))
      (node (ref "VR4") (pin "3") (pinfunction "2_3") (pintype "passive"))
      (node (ref "VR5") (pin "3") (pinfunction "2_3") (pintype "passive"))
    )
    (net (code "88") (name "Net-(DCR1-ADJ)") (class "Default")
      (node (ref "DCR1") (pin "4") (pinfunction "ADJ_4") (pintype "bidirectional"))
      (node (ref "R1") (pin "2") (pinfunction "2_2") (pintype "passive"))
    )
    (net (code "89") (name "Net-(DCR2-ADJ)") (class "Default")
      (node (ref "DCR2") (pin "4") (pinfunction "ADJ_4") (pintype "bidirectional"))
      (node (ref "R2") (pin "2") (pinfunction "2_2") (pintype "passive"))
    )
    (net (code "90") (name "Net-(J13-Pad2)") (class "Default")
      (node (ref "J13") (pin "2") (pinfunction "2_2") (pintype "passive"))
      (node (ref "J13") (pin "3") (pinfunction "3_3") (pintype "passive"))
    )
    (net (code "91") (name "Net-(R1-Pad1)") (class "Default")
      (node (ref "R1") (pin "1") (pinfunction "1_1") (pintype "passive"))
      (node (ref "R15") (pin "2") (pinfunction "2_2") (pintype "passive"))
    )
    (net (code "92") (name "Net-(R16-Pad2)") (class "Default")
      (node (ref "R16") (pin "2") (pinfunction "2_2") (pintype "passive"))
      (node (ref "R2") (pin "1") (pinfunction "1_1") (pintype "passive"))
    )
    (net (code "93") (name "Net-(U1-ISEN)") (class "Default")
      (node (ref "R4") (pin "2") (pinfunction "2_2") (pintype "passive"))
      (node (ref "U1") (pin "7") (pinfunction "ISEN_7") (pintype "passive"))
    )
    (net (code "94") (name "Net-(U1-OUT1)") (class "Default")
      (node (ref "J5") (pin "6") (pinfunction "6_6") (pintype "passive"))
      (node (ref "U1") (pin "6") (pinfunction "OUT1_6") (pintype "passive"))
    )
    (net (code "95") (name "Net-(U1-OUT2)") (class "Default")
      (node (ref "J5") (pin "5") (pinfunction "5_5") (pintype "passive"))
      (node (ref "U1") (pin "8") (pinfunction "OUT2_8") (pintype "passive"))
    )
    (net (code "96") (name "Net-(U1-VM)") (class "Default")
      (node (ref "C8") (pin "1") (pinfunction "1_1") (pintype "passive"))
      (node (ref "C9") (pin "1") (pinfunction "1_1") (pintype "passive"))
      (node (ref "R8") (pin "2") (pinfunction "2_2") (pintype "passive"))
      (node (ref "U1") (pin "5") (pinfunction "VM_5") (pintype "passive"))
      (node (ref "U5") (pin "2") (pinfunction "RS1-_2") (pintype "passive"))
    )
    (net (code "97") (name "Net-(U2-ISEN)") (class "Default")
      (node (ref "R5") (pin "2") (pinfunction "2_2") (pintype "passive"))
      (node (ref "U2") (pin "7") (pinfunction "ISEN_7") (pintype "passive"))
    )
    (net (code "98") (name "Net-(U2-OUT1)") (class "Default")
      (node (ref "J6") (pin "2") (pinfunction "2_2") (pintype "passive"))
      (node (ref "U2") (pin "6") (pinfunction "OUT1_6") (pintype "passive"))
    )
    (net (code "99") (name "Net-(U2-OUT2)") (class "Default")
      (node (ref "J6") (pin "1") (pinfunction "1_1") (pintype "passive"))
      (node (ref "U2") (pin "8") (pinfunction "OUT2_8") (pintype "passive"))
    )
    (net (code "100") (name "Net-(U2-VM)") (class "Default")
      (node (ref "C10") (pin "1") (pinfunction "1_1") (pintype "passive"))
      (node (ref "C11") (pin "1") (pinfunction "1_1") (pintype "passive"))
      (node (ref "R9") (pin "2") (pinfunction "2_2") (pintype "passive"))
      (node (ref "U2") (pin "5") (pinfunction "VM_5") (pintype "passive"))
      (node (ref "U5") (pin "6") (pinfunction "RS2-_6") (pintype "passive"))
    )
    (net (code "101") (name "Net-(U3-ISEN)") (class "Default")
      (node (ref "R6") (pin "2") (pinfunction "2_2") (pintype "passive"))
      (node (ref "U3") (pin "7") (pinfunction "ISEN_7") (pintype "passive"))
    )
    (net (code "102") (name "Net-(U3-OUT1)") (class "Default")
      (node (ref "J7") (pin "2") (pinfunction "2_2") (pintype "passive"))
      (node (ref "U3") (pin "6") (pinfunction "OUT1_6") (pintype "passive"))
    )
    (net (code "103") (name "Net-(U3-OUT2)") (class "Default")
      (node (ref "J7") (pin "1") (pinfunction "1_1") (pintype "passive"))
      (node (ref "U3") (pin "8") (pinfunction "OUT2_8") (pintype "passive"))
    )
    (net (code "104") (name "Net-(U3-VM)") (class "Default")
      (node (ref "C12") (pin "1") (pinfunction "1_1") (pintype "passive"))
      (node (ref "C13") (pin "1") (pinfunction "1_1") (pintype "passive"))
      (node (ref "R10") (pin "1") (pinfunction "1_1") (pintype "passive"))
      (node (ref "U3") (pin "5") (pinfunction "VM_5") (pintype "passive"))
      (node (ref "U5") (pin "9") (pinfunction "RS3-_9") (pintype "passive"))
    )
    (net (code "105") (name "Net-(U4-ISEN)") (class "Default")
      (node (ref "R7") (pin "2") (pinfunction "2_2") (pintype "passive"))
      (node (ref "U4") (pin "7") (pinfunction "ISEN_7") (pintype "passive"))
    )
    (net (code "106") (name "Net-(U4-OUT1)") (class "Default")
      (node (ref "J5") (pin "4") (pinfunction "4_4") (pintype "passive"))
      (node (ref "U4") (pin "6") (pinfunction "OUT1_6") (pintype "passive"))
    )
    (net (code "107") (name "Net-(U4-OUT2)") (class "Default")
      (node (ref "J5") (pin "3") (pinfunction "3_3") (pintype "passive"))
      (node (ref "U4") (pin "8") (pinfunction "OUT2_8") (pintype "passive"))
    )
    (net (code "108") (name "Net-(U4-VM)") (class "Default")
      (node (ref "C14") (pin "1") (pinfunction "1_1") (pintype "passive"))
      (node (ref "C15") (pin "1") (pinfunction "1_1") (pintype "passive"))
      (node (ref "R11") (pin "1") (pinfunction "1_1") (pintype "passive"))
      (node (ref "U4") (pin "5") (pinfunction "VM_5") (pintype "passive"))
      (node (ref "U5") (pin "13") (pinfunction "RS4-_13") (pintype "passive"))
    )
    (net (code "109") (name "Net-(U6-ISEN)") (class "Default")
      (node (ref "R17") (pin "2") (pinfunction "2_2") (pintype "passive"))
      (node (ref "U6") (pin "7") (pinfunction "ISEN_7") (pintype "passive"))
    )
    (net (code "110") (name "Net-(U6-OUT1)") (class "Default")
      (node (ref "J5") (pin "2") (pinfunction "2_2") (pintype "passive"))
      (node (ref "U6") (pin "6") (pinfunction "OUT1_6") (pintype "passive"))
    )
    (net (code "111") (name "Net-(U6-OUT2)") (class "Default")
      (node (ref "J5") (pin "1") (pinfunction "1_1") (pintype "passive"))
      (node (ref "U6") (pin "8") (pinfunction "OUT2_8") (pintype "passive"))
    )
    (net (code "112") (name "Net-(U7-DM)") (class "Default")
      (node (ref "J14") (pin "2") (pinfunction "2_2") (pintype "passive"))
      (node (ref "U7") (pin "7") (pinfunction "DM_7") (pintype "passive"))
    )
    (net (code "113") (name "Net-(U7-DP)") (class "Default")
      (node (ref "J14") (pin "3") (pinfunction "3_3") (pintype "passive"))
      (node (ref "U7") (pin "6") (pinfunction "DP_6") (pintype "passive"))
    )
    (net (code "114") (name "Net-(U7-EN)") (class "Default")
      (node (ref "R18") (pin "2") (pinfunction "2_2") (pintype "passive"))
      (node (ref "U7") (pin "5") (pinfunction "EN_5") (pintype "passive"))
    )
    (net (code "115") (name "Net-(U7-ILIM_)") (class "Default")
      (node (ref "R19") (pin "2") (pinfunction "2_2") (pintype "passive"))
      (node (ref "U7") (pin "2") (pinfunction "ILIM__2") (pintype "passive"))
    )
    (net (code "116") (name "Net-(U7-OUT)") (class "Default")
      (node (ref "C19") (pin "1") (pinfunction "1_1") (pintype "passive"))
      (node (ref "J14") (pin "1") (pinfunction "1_1") (pintype "passive"))
      (node (ref "U7") (pin "8") (pinfunction "OUT_8") (pintype "passive"))
    )
    (net (code "117") (name "unconnected-(CN-A-Pad15)") (class "Default")
      (node (ref "CN-A") (pin "15") (pinfunction "15_15") (pintype "passive"))
    )
    (net (code "118") (name "unconnected-(CN-A-Pad16)") (class "Default")
      (node (ref "CN-A") (pin "16") (pinfunction "16_16") (pintype "passive"))
    )
    (net (code "119") (name "unconnected-(CN-A-Pad23)") (class "Default")
      (node (ref "CN-A") (pin "23") (pinfunction "23_23") (pintype "passive"))
    )
    (net (code "120") (name "unconnected-(CN-A-Pad24)") (class "Default")
      (node (ref "CN-A") (pin "24") (pinfunction "24_24") (pintype "passive"))
    )
    (net (code "121") (name "unconnected-(CN-A-Pad27)") (class "Default")
      (node (ref "CN-A") (pin "27") (pinfunction "27_27") (pintype "passive"))
    )
    (net (code "122") (name "unconnected-(CN-A-Pad28)") (class "Default")
      (node (ref "CN-A") (pin "28") (pinfunction "28_28") (pintype "passive"))
    )
    (net (code "123") (name "unconnected-(CN-A-Pad34)") (class "Default")
      (node (ref "CN-A") (pin "34") (pinfunction "34_34") (pintype "passive"))
    )
    (net (code "124") (name "unconnected-(CN-B-Pad2)") (class "Default")
      (node (ref "CN-B") (pin "2") (pinfunction "2_2") (pintype "passive"))
    )
    (net (code "125") (name "unconnected-(CN-B-Pad4)") (class "Default")
      (node (ref "CN-B") (pin "4") (pinfunction "4_4") (pintype "passive"))
    )
    (net (code "126") (name "unconnected-(CN-B-Pad6)") (class "Default")
      (node (ref "CN-B") (pin "6") (pinfunction "6_6") (pintype "passive"))
    )
    (net (code "127") (name "unconnected-(CN-B-Pad20)") (class "Default")
      (node (ref "CN-B") (pin "20") (pinfunction "20_20") (pintype "passive"))
    )
    (net (code "128") (name "unconnected-(CN-B-Pad22)") (class "Default")
      (node (ref "CN-B") (pin "22") (pinfunction "22_22") (pintype "passive"))
    )
    (net (code "129") (name "unconnected-(CN-B-Pad24)") (class "Default")
      (node (ref "CN-B") (pin "24") (pinfunction "24_24") (pintype "passive"))
    )
    (net (code "130") (name "unconnected-(CN-B-Pad26)") (class "Default")
      (node (ref "CN-B") (pin "26") (pinfunction "26_26") (pintype "passive"))
    )
    (net (code "131") (name "unconnected-(CN-B-Pad27)") (class "Default")
      (node (ref "CN-B") (pin "27") (pinfunction "27_27") (pintype "passive"))
    )
    (net (code "132") (name "unconnected-(CN-B-Pad28)") (class "Default")
      (node (ref "CN-B") (pin "28") (pinfunction "28_28") (pintype "passive"))
    )
    (net (code "133") (name "unconnected-(CN-B-Pad29)") (class "Default")
      (node (ref "CN-B") (pin "29") (pinfunction "29_29") (pintype "passive"))
    )
    (net (code "134") (name "unconnected-(CN-B-Pad30)") (class "Default")
      (node (ref "CN-B") (pin "30") (pinfunction "30_30") (pintype "passive"))
    )
    (net (code "135") (name "unconnected-(CN-B-Pad31)") (class "Default")
      (node (ref "CN-B") (pin "31") (pinfunction "31_31") (pintype "passive"))
    )
    (net (code "136") (name "unconnected-(CN-B-Pad32)") (class "Default")
      (node (ref "CN-B") (pin "32") (pinfunction "32_32") (pintype "passive"))
    )
    (net (code "137") (name "unconnected-(CN-B-Pad37)") (class "Default")
      (node (ref "CN-B") (pin "37") (pinfunction "37_37") (pintype "passive"))
    )
    (net (code "138") (name "unconnected-(CN-B-Pad38)") (class "Default")
      (node (ref "CN-B") (pin "38") (pinfunction "38_38") (pintype "passive"))
    )
    (net (code "139") (name "unconnected-(DCR1-*INH-Pad3)") (class "Default")
      (node (ref "DCR1") (pin "3") (pinfunction "*INH_3") (pintype "bidirectional"))
    )
    (net (code "140") (name "unconnected-(DCR2-*INH-Pad3)") (class "Default")
      (node (ref "DCR2") (pin "3") (pinfunction "*INH_3") (pintype "bidirectional"))
    )
    (net (code "141") (name "unconnected-(J8-Pad7)") (class "Default")
      (node (ref "J8") (pin "7") (pinfunction "7_7") (pintype "passive"))
    )
    (net (code "142") (name "unconnected-(J8-Pad8)") (class "Default")
      (node (ref "J8") (pin "8") (pinfunction "8_8") (pintype "passive"))
    )
    (net (code "143") (name "unconnected-(J8-Pad9)") (class "Default")
      (node (ref "J8") (pin "9") (pinfunction "9_9") (pintype "passive"))
    )
    (net (code "144") (name "unconnected-(J8-Pad10)") (class "Default")
      (node (ref "J8") (pin "10") (pinfunction "10_10") (pintype "passive"))
    )
    (net (code "145") (name "unconnected-(J9-Pad10)") (class "Default")
      (node (ref "J9") (pin "10") (pinfunction "10_10") (pintype "passive"))
    )
    (net (code "146") (name "unconnected-(J13-Pad15)") (class "Default")
      (node (ref "J13") (pin "15") (pinfunction "15_15") (pintype "passive"))
    )
    (net (code "147") (name "unconnected-(J13-Pad16)") (class "Default")
      (node (ref "J13") (pin "16") (pinfunction "16_16") (pintype "passive"))
    )
    (net (code "148") (name "unconnected-(J13-Pad17)") (class "Default")
      (node (ref "J13") (pin "17") (pinfunction "17_17") (pintype "passive"))
    )
    (net (code "149") (name "unconnected-(J13-Pad18)") (class "Default")
      (node (ref "J13") (pin "18") (pinfunction "18_18") (pintype "passive"))
    )
    (net (code "150") (name "unconnected-(U7-{slash}CS-Pad4)") (class "Default")
      (node (ref "U7") (pin "4") (pinfunction "/CS_4") (pintype "passive"))
    )
  )
)
